# front_io.net
KiCad netlist of a schematic drawn in Altium Designer
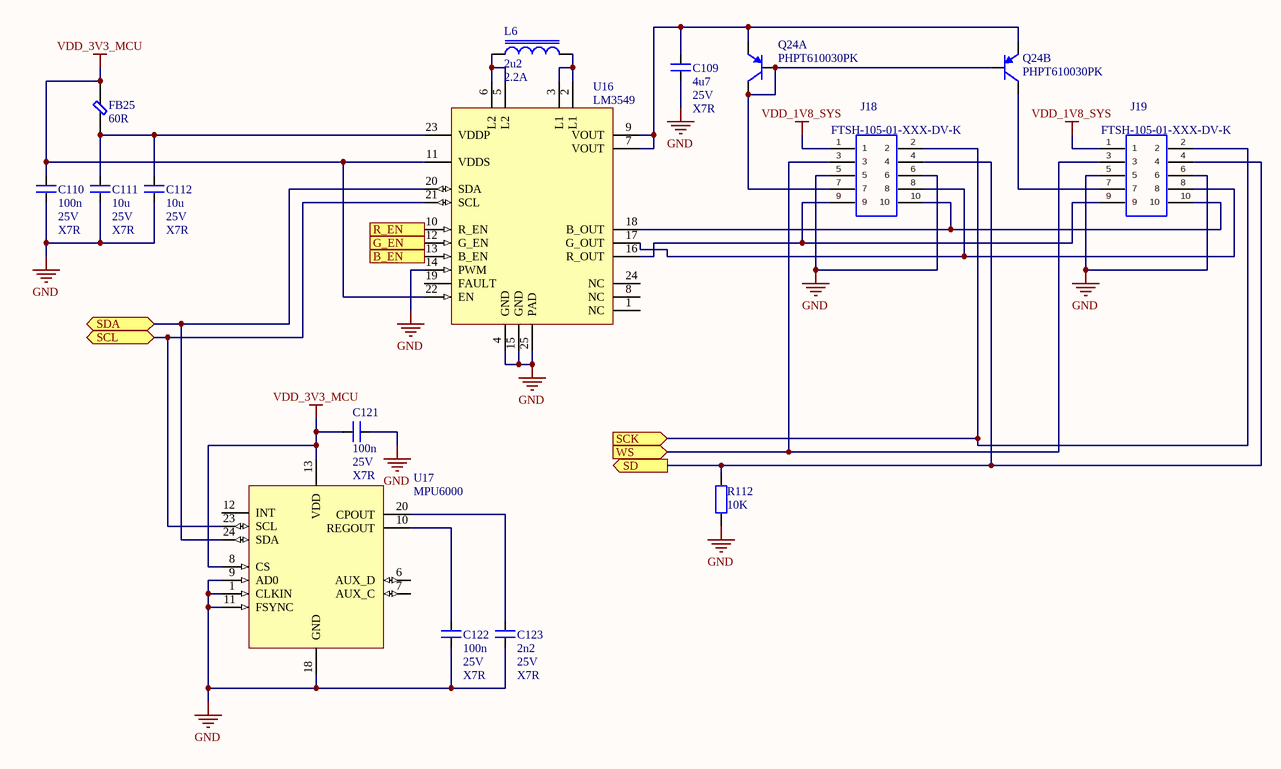
[diagram p0: front_io.SchDoc]

(export (version "E")
  (design (tool "Eeschema 10.0.6"))
  (components
    (comp (ref "C109")
      (value "4u7")
      (footprint "C3216[1206]")
      (description "Capacitor")
      (fields (field (name "VOLTAGE") "25V") (field (name "TYPE") "X7R") (field (name "Comment") "cap"))
      (libsource (lib "gpa_passives") (part "cap"))
    )
    (comp (ref "C110")
      (value "100n")
      (footprint "C1005[0402]")
      (description "Capacitor")
      (fields (field (name "VOLTAGE") "25V") (field (name "TYPE") "X7R") (field (name "Comment") "cap"))
      (libsource (lib "gpa_passives") (part "cap"))
    )
    (comp (ref "C111")
      (value "10u")
      (footprint "C3216[1206]")
      (description "Capacitor")
      (fields (field (name "VOLTAGE") "25V") (field (name "TYPE") "X7R") (field (name "Comment") "cap"))
      (libsource (lib "gpa_passives") (part "cap"))
    )
    (comp (ref "C112")
      (value "10u")
      (footprint "C3216[1206]")
      (description "Capacitor")
      (fields (field (name "VOLTAGE") "25V") (field (name "TYPE") "X7R") (field (name "Comment") "cap"))
      (libsource (lib "gpa_passives") (part "cap"))
    )
    (comp (ref "C121")
      (value "100n")
      (footprint "C1005[0402]")
      (description "Capacitor")
      (fields (field (name "VOLTAGE") "25V") (field (name "TYPE") "X7R") (field (name "Comment") "cap"))
      (libsource (lib "gpa_passives") (part "cap"))
    )
    (comp (ref "C122")
      (value "100n")
      (footprint "C1005[0402]")
      (description "Capacitor")
      (fields (field (name "VOLTAGE") "25V") (field (name "TYPE") "X7R") (field (name "Comment") "cap"))
      (libsource (lib "gpa_passives") (part "cap"))
    )
    (comp (ref "C123")
      (value "2n2")
      (footprint "C1005[0402]")
      (description "Capacitor")
      (fields (field (name "VOLTAGE") "25V") (field (name "TYPE") "X7R") (field (name "Comment") "cap"))
      (libsource (lib "gpa_passives") (part "cap"))
    )
    (comp (ref "FB25")
      (value "60R")
      (footprint "FBC1608X07N")
      (description "Ferrite bead")
      (libsource (lib "gpa_passives") (part "ferrite_bead"))
    )
    (comp (ref "J18")
      (value "FTSH-105-01-XXX-DV-K")
      (footprint "FTSH-105-01-XXX-DV-K")
      (description "TERMINAL STRIP, .050\"(1.27mm) PITCH, 10 PINS, KEYED")
      (fields (field (name "MANUFACTURER") "SAMTEC") (field (name "CREATED") "November 30, 2016 - Wendy Xin"))
      (libsource (lib "FTSH-105-01-XXX-DV-K") (part "FTSH-105-01-XXX-DV-K"))
    )
    (comp (ref "J19")
      (value "FTSH-105-01-XXX-DV-K")
      (footprint "FTSH-105-01-XXX-DV-K")
      (description "TERMINAL STRIP, .050\"(1.27mm) PITCH, 10 PINS, KEYED")
      (fields (field (name "MANUFACTURER") "SAMTEC") (field (name "CREATED") "November 30, 2016 - Wendy Xin"))
      (libsource (lib "FTSH-105-01-XXX-DV-K") (part "FTSH-105-01-XXX-DV-K"))
    )
    (comp (ref "L6")
      (value "2u2")
      (footprint "YUDEN_NRS4018T-XXXMDGJ")
      (fields (field (name "CURRENT") "2.2A") (field (name "Comment") "ASPI-0630LR-XXXM-T15"))
      (libsource (lib "gpa_passives") (part "ind"))
    )
    (comp (ref "Q24")
      (value "PHPT610030PK")
      (footprint "NXP_LFPAK56D127P610X105-8N")
      (description "PNP Bipolar Transistor")
      (fields (field (name "PUBLISHER") "Altium Limited"))
      (libsource (lib "gpa_actives") (part "pnp_bipolar_dual"))
    )
    (comp (ref "R112")
      (value "10K")
      (footprint "R1005[0402]")
      (description "Resistor")
      (fields (field (name "TOLERANCE") "5%") (field (name "Comment") "res"))
      (libsource (lib "gpa_passives") (part "res"))
    )
    (comp (ref "U16")
      (value "LM3549")
      (footprint "TI_QFN50P400X400X80_HS-25M")
      (libsource (lib "gpa_ti") (part "lm3549"))
    )
    (comp (ref "U17")
      (value "MPU6000")
      (footprint "INVSENSE_QFN50P400X400X95_HS-25M")
      (libsource (lib "gpa_invensense") (part "invsense_mpu6000"))
    )
  )
  (nets
    (net (code "1") (name "/B_EN") (class "Default")
      (node (ref "U16") (pin "13") (pinfunction "B_EN_13") (pintype "input"))
    )
    (net (code "2") (name "/G_EN") (class "Default")
      (node (ref "U16") (pin "12") (pinfunction "G_EN_12") (pintype "input"))
    )
    (net (code "3") (name "/R_EN") (class "Default")
      (node (ref "U16") (pin "10") (pinfunction "R_EN_10") (pintype "input"))
    )
    (net (code "4") (name "/SCK") (class "Default")
      (node (ref "J18") (pin "2") (pinfunction "2_2") (pintype "passive"))
      (node (ref "J19") (pin "2") (pinfunction "2_2") (pintype "passive"))
    )
    (net (code "5") (name "/SCL") (class "Default")
      (node (ref "U16") (pin "21") (pinfunction "SCL_21") (pintype "bidirectional"))
      (node (ref "U17") (pin "23") (pinfunction "SCL_23") (pintype "bidirectional"))
    )
    (net (code "6") (name "/SD") (class "Default")
      (node (ref "J18") (pin "4") (pinfunction "4_4") (pintype "passive"))
      (node (ref "J19") (pin "4") (pinfunction "4_4") (pintype "passive"))
      (node (ref "R112") (pin "2") (pinfunction "2_2") (pintype "passive"))
    )
    (net (code "7") (name "/SDA") (class "Default")
      (node (ref "U16") (pin "20") (pinfunction "SDA_20") (pintype "bidirectional"))
      (node (ref "U17") (pin "24") (pinfunction "SDA_24") (pintype "bidirectional"))
    )
    (net (code "8") (name "/WS") (class "Default")
      (node (ref "J18") (pin "3") (pinfunction "3_3") (pintype "passive"))
      (node (ref "J19") (pin "3") (pinfunction "3_3") (pintype "passive"))
    )
    (net (code "9") (name "GND") (class "Default")
      (node (ref "C109") (pin "1") (pinfunction "1_1") (pintype "passive"))
      (node (ref "C110") (pin "1") (pinfunction "1_1") (pintype "passive"))
      (node (ref "C111") (pin "1") (pinfunction "1_1") (pintype "passive"))
      (node (ref "C112") (pin "1") (pinfunction "1_1") (pintype "passive"))
      (node (ref "C121") (pin "2") (pinfunction "2_2") (pintype "passive"))
      (node (ref "C122") (pin "2") (pinfunction "2_2") (pintype "passive"))
      (node (ref "C123") (pin "2") (pinfunction "2_2") (pintype "passive"))
      (node (ref "J18") (pin "5") (pinfunction "5_5") (pintype "passive"))
      (node (ref "J18") (pin "6") (pinfunction "6_6") (pintype "passive"))
      (node (ref "J19") (pin "5") (pinfunction "5_5") (pintype "passive"))
      (node (ref "J19") (pin "6") (pinfunction "6_6") (pintype "passive"))
      (node (ref "R112") (pin "1") (pinfunction "1_1") (pintype "passive"))
      (node (ref "U16") (pin "14") (pinfunction "PWM_14") (pintype "input"))
      (node (ref "U16") (pin "15") (pinfunction "GND_15") (pintype "power_in"))
      (node (ref "U16") (pin "25") (pinfunction "PAD_25") (pintype "power_in"))
      (node (ref "U16") (pin "4") (pinfunction "GND_4") (pintype "power_in"))
      (node (ref "U17") (pin "1") (pinfunction "CLKIN_1") (pintype "input"))
      (node (ref "U17") (pin "11") (pinfunction "FSYNC_11") (pintype "input"))
      (node (ref "U17") (pin "18") (pinfunction "GND_18") (pintype "power_in"))
      (node (ref "U17") (pin "9") (pinfunction "AD0_9") (pintype "input"))
    )
    (net (code "10") (name "Net-(C109-Pad2)") (class "Default")
      (node (ref "C109") (pin "2") (pinfunction "2_2") (pintype "passive"))
      (node (ref "Q24") (pin "E1") (pinfunction "E1_E1") (pintype "passive"))
      (node (ref "Q24") (pin "E2") (pinfunction "E2_E2") (pintype "passive"))
      (node (ref "U16") (pin "7") (pinfunction "VOUT_7") (pintype "power_in"))
      (node (ref "U16") (pin "9") (pinfunction "VOUT_9") (pintype "power_in"))
    )
    (net (code "11") (name "Net-(J18-Pad7)") (class "Default")
      (node (ref "J18") (pin "7") (pinfunction "7_7") (pintype "passive"))
      (node (ref "Q24") (pin "B1") (pinfunction "B1_B1") (pintype "passive"))
      (node (ref "Q24") (pin "B2") (pinfunction "B2_B2") (pintype "passive"))
      (node (ref "Q24") (pin "C1") (pinfunction "C1_C1") (pintype "passive"))
    )
    (net (code "12") (name "Net-(J19-Pad7)") (class "Default")
      (node (ref "J19") (pin "7") (pinfunction "7_7") (pintype "passive"))
      (node (ref "Q24") (pin "C2") (pinfunction "C2_C2") (pintype "passive"))
    )
    (net (code "13") (name "Net-(L6-Pad1)") (class "Default")
      (node (ref "L6") (pin "1") (pinfunction "1_1") (pintype "passive"))
      (node (ref "U16") (pin "5") (pinfunction "L2_5") (pintype "power_in"))
      (node (ref "U16") (pin "6") (pinfunction "L2_6") (pintype "power_in"))
    )
    (net (code "14") (name "Net-(L6-Pad2)") (class "Default")
      (node (ref "L6") (pin "2") (pinfunction "2_2") (pintype "passive"))
      (node (ref "U16") (pin "2") (pinfunction "L1_2") (pintype "power_in"))
      (node (ref "U16") (pin "3") (pinfunction "L1_3") (pintype "power_in"))
    )
    (net (code "15") (name "Net-(U16-B_OUT)") (class "Default")
      (node (ref "J18") (pin "10") (pinfunction "10_10") (pintype "passive"))
      (node (ref "J19") (pin "10") (pinfunction "10_10") (pintype "passive"))
      (node (ref "U16") (pin "18") (pinfunction "B_OUT_18") (pintype "open_emitter"))
    )
    (net (code "16") (name "Net-(U16-G_OUT)") (class "Default")
      (node (ref "J18") (pin "8") (pinfunction "8_8") (pintype "passive"))
      (node (ref "J19") (pin "8") (pinfunction "8_8") (pintype "passive"))
      (node (ref "U16") (pin "17") (pinfunction "G_OUT_17") (pintype "open_emitter"))
    )
    (net (code "17") (name "Net-(U16-R_OUT)") (class "Default")
      (node (ref "J18") (pin "9") (pinfunction "9_9") (pintype "passive"))
      (node (ref "J19") (pin "9") (pinfunction "9_9") (pintype "passive"))
      (node (ref "U16") (pin "16") (pinfunction "R_OUT_16") (pintype "open_emitter"))
    )
    (net (code "18") (name "Net-(U16-VDDP)") (class "Default")
      (node (ref "C111") (pin "2") (pinfunction "2_2") (pintype "passive"))
      (node (ref "C112") (pin "2") (pinfunction "2_2") (pintype "passive"))
      (node (ref "FB25") (pin "1") (pinfunction "1_1") (pintype "passive"))
      (node (ref "U16") (pin "23") (pinfunction "VDDP_23") (pintype "power_in"))
    )
    (net (code "19") (name "Net-(U17-CPOUT)") (class "Default")
      (node (ref "C123") (pin "1") (pinfunction "1_1") (pintype "passive"))
      (node (ref "U17") (pin "20") (pinfunction "CPOUT_20") (pintype "power_in"))
    )
    (net (code "20") (name "Net-(U17-REGOUT)") (class "Default")
      (node (ref "C122") (pin "1") (pinfunction "1_1") (pintype "passive"))
      (node (ref "U17") (pin "10") (pinfunction "REGOUT_10") (pintype "power_in"))
    )
    (net (code "21") (name "VDD_1V8_SYS") (class "Default")
      (node (ref "J18") (pin "1") (pinfunction "1_1") (pintype "passive"))
      (node (ref "J19") (pin "1") (pinfunction "1_1") (pintype "passive"))
    )
    (net (code "22") (name "VDD_3V3_MCU") (class "Default")
      (node (ref "C110") (pin "2") (pinfunction "2_2") (pintype "passive"))
      (node (ref "C121") (pin "1") (pinfunction "1_1") (pintype "passive"))
      (node (ref "FB25") (pin "2") (pinfunction "2_2") (pintype "passive"))
      (node (ref "U16") (pin "11") (pinfunction "VDDS_11") (pintype "power_in"))
      (node (ref "U16") (pin "22") (pinfunction "EN_22") (pintype "input"))
      (node (ref "U17") (pin "13") (pinfunction "VDD_13") (pintype "power_in"))
      (node (ref "U17") (pin "8") (pinfunction "CS_8") (pintype "input"))
    )
    (net (code "23") (name "unconnected-(U16-FAULT-Pad19)") (class "Default")
      (node (ref "U16") (pin "19") (pinfunction "FAULT_19") (pintype "open_collector"))
    )
    (net (code "24") (name "unconnected-(U16-NC-Pad1)") (class "Default")
      (node (ref "U16") (pin "1") (pinfunction "NC_1") (pintype "passive"))
    )
    (net (code "25") (name "unconnected-(U16-NC-Pad8)") (class "Default")
      (node (ref "U16") (pin "8") (pinfunction "NC_8") (pintype "passive"))
    )
    (net (code "26") (name "unconnected-(U16-NC-Pad24)") (class "Default")
      (node (ref "U16") (pin "24") (pinfunction "NC_24") (pintype "passive"))
    )
    (net (code "27") (name "unconnected-(U17-AUX_C-Pad7)") (class "Default")
      (node (ref "U17") (pin "7") (pinfunction "AUX_C_7") (pintype "bidirectional"))
    )
    (net (code "28") (name "unconnected-(U17-AUX_D-Pad6)") (class "Default")
      (node (ref "U17") (pin "6") (pinfunction "AUX_D_6") (pintype "bidirectional"))
    )
    (net (code "29") (name "unconnected-(U17-INT-Pad12)") (class "Default")
      (node (ref "U17") (pin "12") (pinfunction "INT_12") (pintype "open_collector"))
    )
  )
)
